# linda-arduino-sensor.net
KiCad netlist of a schematic drawn in EAGLE
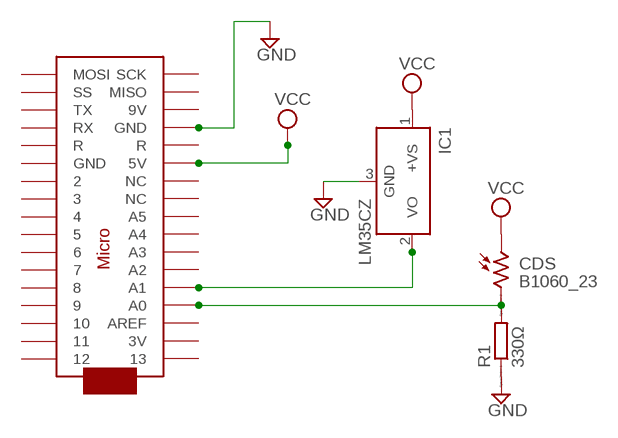
[diagram p0: schematic, sheet 1]

(export (version "E")
  (design (tool "Eeschema 10.0.6"))
  (components
    (comp (ref "CDS")
      (value "B1060_23")
      (footprint "eagle-import:TO-8_B10")
      (libsource (lib "eagle-import") (part "?1060B_23"))
    )
    (comp (ref "IC1")
      (value "LM35CZ")
      (footprint "eagle-import:TO92")
      (libsource (lib "eagle-import") (part "LM35CZ"))
    )
    (comp (ref "R1")
      (value "330Ω")
      (footprint "eagle-import:0207_10")
      (libsource (lib "eagle-import") (part "R0207/10"))
    )
    (comp (ref "U$1")
      (value "ARDUINOMICRO")
      (footprint "eagle-import:ARDUINOMICRO")
      (libsource (lib "eagle-import") (part "ARDUINOMICRO"))
    )
  )
  (nets
    (net (code "1") (name "GND") (class "Default")
      (node (ref "IC1") (pin "3") (pinfunction "GND_3") (pintype "power_in"))
      (node (ref "R1") (pin "1") (pinfunction "1_1") (pintype "passive"))
      (node (ref "U$1") (pin "P$12") (pinfunction "GND_P$12") (pintype "bidirectional"))
    )
    (net (code "2") (name "Net-(IC1-VO)") (class "Default")
      (node (ref "IC1") (pin "2") (pinfunction "VO_2") (pintype "input"))
      (node (ref "U$1") (pin "P$30") (pinfunction "A1_P$30") (pintype "bidirectional"))
    )
    (net (code "3") (name "Net-(U$1-A0)") (class "Default")
      (node (ref "CDS") (pin "2") (pinfunction "2_2") (pintype "passive"))
      (node (ref "R1") (pin "2") (pinfunction "2_2") (pintype "passive"))
      (node (ref "U$1") (pin "P$31") (pinfunction "A0_P$31") (pintype "bidirectional"))
    )
    (net (code "4") (name "VCC") (class "Default")
      (node (ref "CDS") (pin "1") (pinfunction "1_1") (pintype "passive"))
      (node (ref "IC1") (pin "1") (pinfunction "+VS_1") (pintype "input"))
      (node (ref "U$1") (pin "P$23") (pinfunction "5V_P$23") (pintype "bidirectional"))
    )
    (net (code "5") (name "unconnected-(U$1-2-PadP$11)") (class "Default")
      (node (ref "U$1") (pin "P$11") (pinfunction "2_P$11") (pintype "bidirectional"))
    )
    (net (code "6") (name "unconnected-(U$1-3-PadP$10)") (class "Default")
      (node (ref "U$1") (pin "P$10") (pinfunction "3_P$10") (pintype "bidirectional"))
    )
    (net (code "7") (name "unconnected-(U$1-3V-PadP$33)") (class "Default")
      (node (ref "U$1") (pin "P$33") (pinfunction "3V_P$33") (pintype "bidirectional"))
    )
    (net (code "8") (name "unconnected-(U$1-4-PadP$9)") (class "Default")
      (node (ref "U$1") (pin "P$9") (pinfunction "4_P$9") (pintype "bidirectional"))
    )
    (net (code "9") (name "unconnected-(U$1-5-PadP$8)") (class "Default")
      (node (ref "U$1") (pin "P$8") (pinfunction "5_P$8") (pintype "bidirectional"))
    )
    (net (code "10") (name "unconnected-(U$1-6-PadP$7)") (class "Default")
      (node (ref "U$1") (pin "P$7") (pinfunction "6_P$7") (pintype "bidirectional"))
    )
    (net (code "11") (name "unconnected-(U$1-7-PadP$6)") (class "Default")
      (node (ref "U$1") (pin "P$6") (pinfunction "7_P$6") (pintype "bidirectional"))
    )
    (net (code "12") (name "unconnected-(U$1-8-PadP$5)") (class "Default")
      (node (ref "U$1") (pin "P$5") (pinfunction "8_P$5") (pintype "bidirectional"))
    )
    (net (code "13") (name "unconnected-(U$1-9-PadP$4)") (class "Default")
      (node (ref "U$1") (pin "P$4") (pinfunction "9_P$4") (pintype "bidirectional"))
    )
    (net (code "14") (name "unconnected-(U$1-9V-PadP$20)") (class "Default")
      (node (ref "U$1") (pin "P$20") (pinfunction "9V_P$20") (pintype "bidirectional"))
    )
    (net (code "15") (name "unconnected-(U$1-10-PadP$3)") (class "Default")
      (node (ref "U$1") (pin "P$3") (pinfunction "10_P$3") (pintype "bidirectional"))
    )
    (net (code "16") (name "unconnected-(U$1-11-PadP$2)") (class "Default")
      (node (ref "U$1") (pin "P$2") (pinfunction "11_P$2") (pintype "bidirectional"))
    )
    (net (code "17") (name "unconnected-(U$1-12-PadP$1)") (class "Default")
      (node (ref "U$1") (pin "P$1") (pinfunction "12_P$1") (pintype "bidirectional"))
    )
    (net (code "18") (name "unconnected-(U$1-13-PadP$34)") (class "Default")
      (node (ref "U$1") (pin "P$34") (pinfunction "13_P$34") (pintype "bidirectional"))
    )
    (net (code "19") (name "unconnected-(U$1-A2-PadP$29)") (class "Default")
      (node (ref "U$1") (pin "P$29") (pinfunction "A2_P$29") (pintype "bidirectional"))
    )
    (net (code "20") (name "unconnected-(U$1-A3-PadP$28)") (class "Default")
      (node (ref "U$1") (pin "P$28") (pinfunction "A3_P$28") (pintype "bidirectional"))
    )
    (net (code "21") (name "unconnected-(U$1-A4-PadP$27)") (class "Default")
      (node (ref "U$1") (pin "P$27") (pinfunction "A4_P$27") (pintype "bidirectional"))
    )
    (net (code "22") (name "unconnected-(U$1-A5-PadP$26)") (class "Default")
      (node (ref "U$1") (pin "P$26") (pinfunction "A5_P$26") (pintype "bidirectional"))
    )
    (net (code "23") (name "unconnected-(U$1-AREF-PadP$32)") (class "Default")
      (node (ref "U$1") (pin "P$32") (pinfunction "AREF_P$32") (pintype "bidirectional"))
    )
    (net (code "24") (name "unconnected-(U$1-GND-PadP$21)") (class "Default")
      (node (ref "U$1") (pin "P$21") (pinfunction "GND_P$21") (pintype "bidirectional"))
    )
    (net (code "25") (name "unconnected-(U$1-MISO-PadP$19)") (class "Default")
      (node (ref "U$1") (pin "P$19") (pinfunction "MISO_P$19") (pintype "bidirectional"))
    )
    (net (code "26") (name "unconnected-(U$1-MOSI-PadP$17)") (class "Default")
      (node (ref "U$1") (pin "P$17") (pinfunction "MOSI_P$17") (pintype "bidirectional"))
    )
    (net (code "27") (name "unconnected-(U$1-NC-PadP$24)") (class "Default")
      (node (ref "U$1") (pin "P$24") (pinfunction "NC_P$24") (pintype "bidirectional"))
    )
    (net (code "28") (name "unconnected-(U$1-NC-PadP$25)") (class "Default")
      (node (ref "U$1") (pin "P$25") (pinfunction "NC_P$25") (pintype "bidirectional"))
    )
    (net (code "29") (name "unconnected-(U$1-R-PadP$13)") (class "Default")
      (node (ref "U$1") (pin "P$13") (pinfunction "R_P$13") (pintype "bidirectional"))
    )
    (net (code "30") (name "unconnected-(U$1-R-PadP$22)") (class "Default")
      (node (ref "U$1") (pin "P$22") (pinfunction "R_P$22") (pintype "bidirectional"))
    )
    (net (code "31") (name "unconnected-(U$1-RX-PadP$14)") (class "Default")
      (node (ref "U$1") (pin "P$14") (pinfunction "RX_P$14") (pintype "bidirectional"))
    )
    (net (code "32") (name "unconnected-(U$1-SCK-PadP$18)") (class "Default")
      (node (ref "U$1") (pin "P$18") (pinfunction "SCK_P$18") (pintype "bidirectional"))
    )
    (net (code "33") (name "unconnected-(U$1-SS-PadP$16)") (class "Default")
      (node (ref "U$1") (pin "P$16") (pinfunction "SS_P$16") (pintype "bidirectional"))
    )
    (net (code "34") (name "unconnected-(U$1-TX-PadP$15)") (class "Default")
      (node (ref "U$1") (pin "P$15") (pinfunction "TX_P$15") (pintype "bidirectional"))
    )
  )
)
